# XOR_GATE.net
KiCad netlist of a schematic drawn in Altium Designer
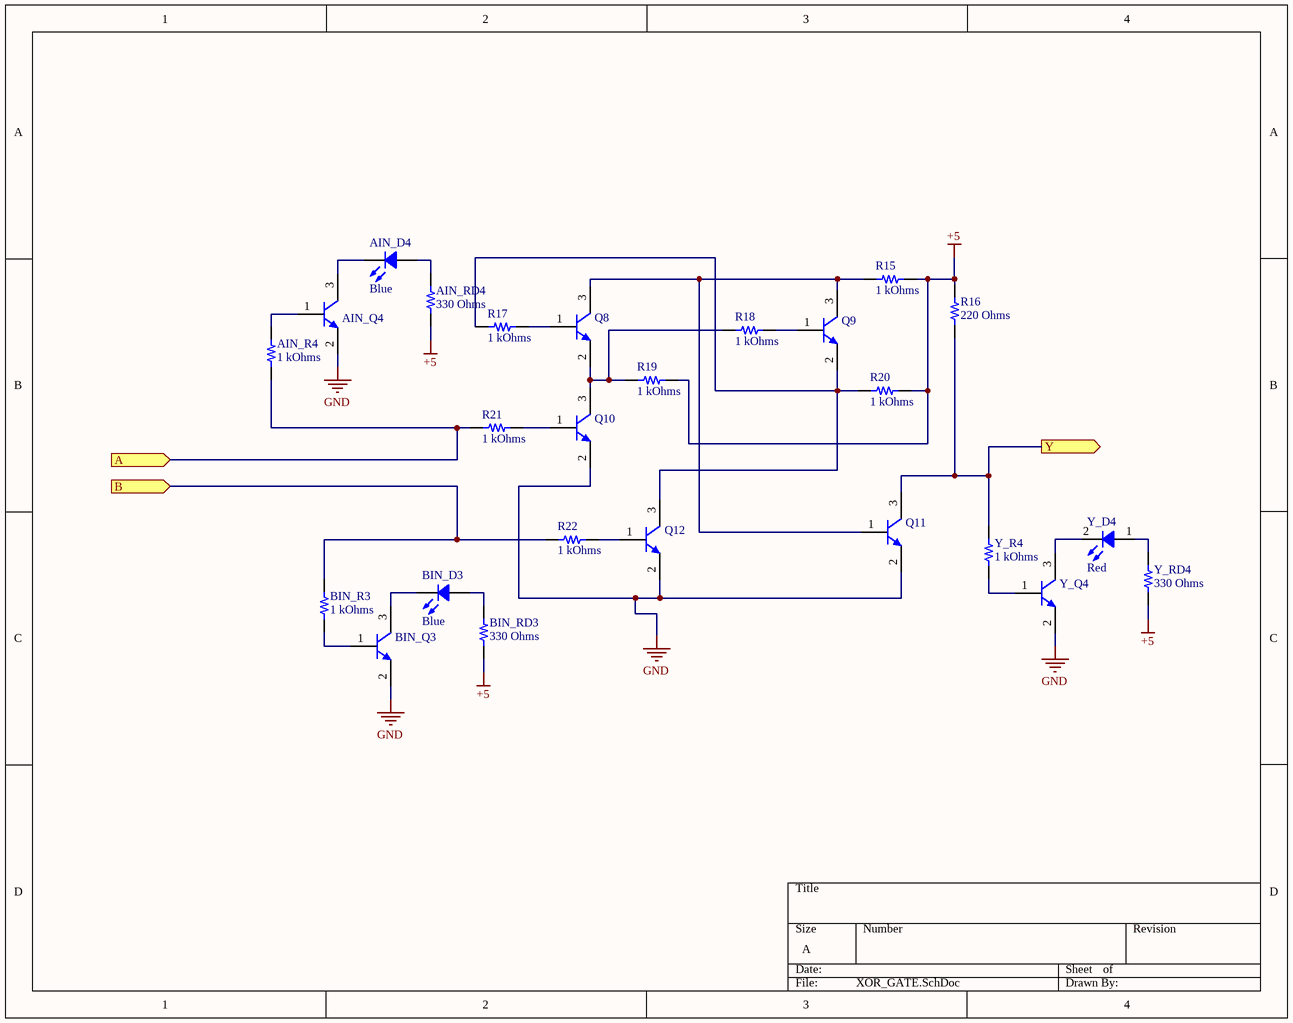
[diagram p0: XOR_GATE.SchDoc]

(export (version "E")
  (design (tool "Eeschema 10.0.6"))
  (components
    (comp (ref "AIN_D4")
      (value "Blue")
      (footprint "LED 0603_1608 BLUE")
      (description "LED BLUE CLEAR 0603 SMD")
      (fields (field (name "PART NUMBER") "IN-S63AT5B") (field (name "MANUFACTURER") "Inolux"))
      (libsource (lib "") (part "LED_1"))
    )
    (comp (ref "AIN_Q4")
      (value "MMSS8050-L-TP")
      (footprint "MCCSEMI SOT-23-3")
      (description "TRANS NPN 25V 1.5A SOT23")
      (fields (field (name "MANUFACTURER") "Micro Commercial Co"))
      (libsource (lib "Celestial Altium Library - altium_library") (part "MCCSEMI NPN SOT-23-3"))
    )
    (comp (ref "AIN_R4")
      (value "1 kOhms")
      (footprint "RES 0603_1608")
      (description "RES SMD 1K OHM 0.1% 1/16W 0603")
      (fields
        (field (name "PART NUMBER") "CPF0603B1K0E")
        (field (name "MANUFACTURER") "TE Connectivity Passive Product")
      )
      (libsource (lib "Celestial Altium Library - altium_library") (part "Resistor"))
    )
    (comp (ref "AIN_RD4")
      (value "330 Ohms")
      (footprint "RES 0603_1608")
      (description "RES 330 OHM 5% 1/10W 0603")
      (fields
        (field (name "PART NUMBER") "RMCF0603JT330R")
        (field (name "MANUFACTURER") "Stackpole Electronics Inc")
      )
      (libsource (lib "Celestial Altium Library - altium_library") (part "Resistor"))
    )
    (comp (ref "BIN_D3")
      (value "Blue")
      (footprint "LED 0603_1608 BLUE")
      (description "LED BLUE CLEAR 0603 SMD")
      (fields (field (name "PART NUMBER") "IN-S63AT5B") (field (name "MANUFACTURER") "Inolux"))
      (libsource (lib "") (part "LED_1"))
    )
    (comp (ref "BIN_Q3")
      (value "MMSS8050-L-TP")
      (footprint "MCCSEMI SOT-23-3")
      (description "TRANS NPN 25V 1.5A SOT23")
      (fields (field (name "MANUFACTURER") "Micro Commercial Co"))
      (libsource (lib "Celestial Altium Library - altium_library") (part "MCCSEMI NPN SOT-23-3"))
    )
    (comp (ref "BIN_R3")
      (value "1 kOhms")
      (footprint "RES 0603_1608")
      (description "RES SMD 1K OHM 0.1% 1/16W 0603")
      (fields
        (field (name "PART NUMBER") "CPF0603B1K0E")
        (field (name "MANUFACTURER") "TE Connectivity Passive Product")
      )
      (libsource (lib "Celestial Altium Library - altium_library") (part "Resistor"))
    )
    (comp (ref "BIN_RD3")
      (value "330 Ohms")
      (footprint "RES 0603_1608")
      (description "RES 330 OHM 5% 1/10W 0603")
      (fields
        (field (name "PART NUMBER") "RMCF0603JT330R")
        (field (name "MANUFACTURER") "Stackpole Electronics Inc")
      )
      (libsource (lib "Celestial Altium Library - altium_library") (part "Resistor"))
    )
    (comp (ref "Q8")
      (value "MMSS8050-L-TP")
      (footprint "MCCSEMI SOT-23-3")
      (description "TRANS NPN 25V 1.5A SOT23")
      (fields (field (name "MANUFACTURER") "Micro Commercial Co"))
      (libsource (lib "Celestial Altium Library - altium_library") (part "MCCSEMI NPN SOT-23-3"))
    )
    (comp (ref "Q9")
      (value "MMSS8050-L-TP")
      (footprint "MCCSEMI SOT-23-3")
      (description "TRANS NPN 25V 1.5A SOT23")
      (fields (field (name "MANUFACTURER") "Micro Commercial Co"))
      (libsource (lib "Celestial Altium Library - altium_library") (part "MCCSEMI NPN SOT-23-3"))
    )
    (comp (ref "Q10")
      (value "MMSS8050-L-TP")
      (footprint "MCCSEMI SOT-23-3")
      (description "TRANS NPN 25V 1.5A SOT23")
      (fields (field (name "MANUFACTURER") "Micro Commercial Co"))
      (libsource (lib "Celestial Altium Library - altium_library") (part "MCCSEMI NPN SOT-23-3"))
    )
    (comp (ref "Q11")
      (value "MMSS8050-L-TP")
      (footprint "MCCSEMI SOT-23-3")
      (description "TRANS NPN 25V 1.5A SOT23")
      (fields (field (name "MANUFACTURER") "Micro Commercial Co"))
      (libsource (lib "Celestial Altium Library - altium_library") (part "MCCSEMI NPN SOT-23-3"))
    )
    (comp (ref "Q12")
      (value "MMSS8050-L-TP")
      (footprint "MCCSEMI SOT-23-3")
      (description "TRANS NPN 25V 1.5A SOT23")
      (fields (field (name "MANUFACTURER") "Micro Commercial Co"))
      (libsource (lib "Celestial Altium Library - altium_library") (part "MCCSEMI NPN SOT-23-3"))
    )
    (comp (ref "R15")
      (value "1 kOhms")
      (footprint "RES 0603_1608")
      (description "RES SMD 1K OHM 0.1% 1/16W 0603")
      (fields
        (field (name "PART NUMBER") "CPF0603B1K0E")
        (field (name "MANUFACTURER") "TE Connectivity Passive Product")
      )
      (libsource (lib "Celestial Altium Library - altium_library") (part "Resistor"))
    )
    (comp (ref "R16")
      (value "220 Ohms")
      (footprint "RES 0603_1608")
      (description "RES SMD 220 OHM 0.5% 1/10W 0603")
      (fields
        (field (name "PART NUMBER") "ERA-3AED221V")
        (field (name "MANUFACTURER") "Panasonic Electronic Components")
      )
      (libsource (lib "Celestial Altium Library - altium_library") (part "Resistor"))
    )
    (comp (ref "R17")
      (value "1 kOhms")
      (footprint "RES 0603_1608")
      (description "RES SMD 1K OHM 0.1% 1/16W 0603")
      (fields
        (field (name "PART NUMBER") "CPF0603B1K0E")
        (field (name "MANUFACTURER") "TE Connectivity Passive Product")
      )
      (libsource (lib "Celestial Altium Library - altium_library") (part "Resistor"))
    )
    (comp (ref "R18")
      (value "1 kOhms")
      (footprint "RES 0603_1608")
      (description "RES SMD 1K OHM 0.1% 1/16W 0603")
      (fields
        (field (name "PART NUMBER") "CPF0603B1K0E")
        (field (name "MANUFACTURER") "TE Connectivity Passive Product")
      )
      (libsource (lib "Celestial Altium Library - altium_library") (part "Resistor"))
    )
    (comp (ref "R19")
      (value "1 kOhms")
      (footprint "RES 0603_1608")
      (description "RES SMD 1K OHM 0.1% 1/16W 0603")
      (fields
        (field (name "PART NUMBER") "CPF0603B1K0E")
        (field (name "MANUFACTURER") "TE Connectivity Passive Product")
      )
      (libsource (lib "Celestial Altium Library - altium_library") (part "Resistor"))
    )
    (comp (ref "R20")
      (value "1 kOhms")
      (footprint "RES 0603_1608")
      (description "RES SMD 1K OHM 0.1% 1/16W 0603")
      (fields
        (field (name "PART NUMBER") "CPF0603B1K0E")
        (field (name "MANUFACTURER") "TE Connectivity Passive Product")
      )
      (libsource (lib "Celestial Altium Library - altium_library") (part "Resistor"))
    )
    (comp (ref "R21")
      (value "1 kOhms")
      (footprint "RES 0603_1608")
      (description "RES SMD 1K OHM 0.1% 1/16W 0603")
      (fields
        (field (name "PART NUMBER") "CPF0603B1K0E")
        (field (name "MANUFACTURER") "TE Connectivity Passive Product")
      )
      (libsource (lib "Celestial Altium Library - altium_library") (part "Resistor"))
    )
    (comp (ref "R22")
      (value "1 kOhms")
      (footprint "RES 0603_1608")
      (description "RES SMD 1K OHM 0.1% 1/16W 0603")
      (fields
        (field (name "PART NUMBER") "CPF0603B1K0E")
        (field (name "MANUFACTURER") "TE Connectivity Passive Product")
      )
      (libsource (lib "Celestial Altium Library - altium_library") (part "Resistor"))
    )
    (comp (ref "Y_D4")
      (value "Red")
      (footprint "LED 0603_1608 RED")
      (description "LED RED CLEAR CHIP SMD")
      (fields (field (name "PART NUMBER") "XZMDK53W-8") (field (name "MANUFACTURER") "SunLED"))
      (libsource (lib "Celestial Altium Library - altium_library") (part "LED"))
    )
    (comp (ref "Y_Q4")
      (value "MMSS8050-L-TP")
      (footprint "MCCSEMI SOT-23-3")
      (description "TRANS NPN 25V 1.5A SOT23")
      (fields (field (name "MANUFACTURER") "Micro Commercial Co"))
      (libsource (lib "Celestial Altium Library - altium_library") (part "MCCSEMI NPN SOT-23-3"))
    )
    (comp (ref "Y_R4")
      (value "1 kOhms")
      (footprint "RES 0603_1608")
      (description "RES SMD 1K OHM 0.1% 1/16W 0603")
      (fields
        (field (name "PART NUMBER") "CPF0603B1K0E")
        (field (name "MANUFACTURER") "TE Connectivity Passive Product")
      )
      (libsource (lib "Celestial Altium Library - altium_library") (part "Resistor"))
    )
    (comp (ref "Y_RD4")
      (value "330 Ohms")
      (footprint "RES 0603_1608")
      (description "RES 330 OHM 5% 1/10W 0603")
      (fields
        (field (name "PART NUMBER") "RMCF0603JT330R")
        (field (name "MANUFACTURER") "Stackpole Electronics Inc")
      )
      (libsource (lib "Celestial Altium Library - altium_library") (part "Resistor"))
    )
  )
  (nets
    (net (code "1") (name "+5") (class "Default")
      (node (ref "AIN_RD4") (pin "1") (pinfunction "1_1") (pintype "passive"))
      (node (ref "BIN_RD3") (pin "1") (pinfunction "1_1") (pintype "passive"))
      (node (ref "R15") (pin "2") (pinfunction "2_2") (pintype "passive"))
      (node (ref "R16") (pin "2") (pinfunction "2_2") (pintype "passive"))
      (node (ref "R19") (pin "2") (pinfunction "2_2") (pintype "passive"))
      (node (ref "R20") (pin "2") (pinfunction "2_2") (pintype "passive"))
      (node (ref "Y_RD4") (pin "1") (pinfunction "1_1") (pintype "passive"))
    )
    (net (code "2") (name "/A") (class "Default")
      (node (ref "AIN_R4") (pin "2") (pinfunction "2_2") (pintype "passive"))
      (node (ref "R21") (pin "1") (pinfunction "1_1") (pintype "passive"))
    )
    (net (code "3") (name "/B") (class "Default")
      (node (ref "BIN_R3") (pin "2") (pinfunction "2_2") (pintype "passive"))
      (node (ref "R22") (pin "1") (pinfunction "1_1") (pintype "passive"))
    )
    (net (code "4") (name "/Y") (class "Default")
      (node (ref "Q11") (pin "3") (pinfunction "C_3") (pintype "passive"))
      (node (ref "R16") (pin "1") (pinfunction "1_1") (pintype "passive"))
      (node (ref "Y_R4") (pin "2") (pinfunction "2_2") (pintype "passive"))
    )
    (net (code "5") (name "GND") (class "Default")
      (node (ref "AIN_Q4") (pin "2") (pinfunction "E_2") (pintype "passive"))
      (node (ref "BIN_Q3") (pin "2") (pinfunction "E_2") (pintype "passive"))
      (node (ref "Q10") (pin "2") (pinfunction "E_2") (pintype "passive"))
      (node (ref "Q11") (pin "2") (pinfunction "E_2") (pintype "passive"))
      (node (ref "Q12") (pin "2") (pinfunction "E_2") (pintype "passive"))
      (node (ref "Y_Q4") (pin "2") (pinfunction "E_2") (pintype "passive"))
    )
    (net (code "6") (name "Net-(AIN_D4-Pad1)") (class "Default")
      (node (ref "AIN_D4") (pin "1") (pinfunction "1_1") (pintype "passive"))
      (node (ref "AIN_RD4") (pin "2") (pinfunction "2_2") (pintype "passive"))
    )
    (net (code "7") (name "Net-(AIN_Q4-B)") (class "Default")
      (node (ref "AIN_Q4") (pin "1") (pinfunction "B_1") (pintype "passive"))
      (node (ref "AIN_R4") (pin "1") (pinfunction "1_1") (pintype "passive"))
    )
    (net (code "8") (name "Net-(AIN_Q4-C)") (class "Default")
      (node (ref "AIN_D4") (pin "2") (pinfunction "2_2") (pintype "passive"))
      (node (ref "AIN_Q4") (pin "3") (pinfunction "C_3") (pintype "passive"))
    )
    (net (code "9") (name "Net-(BIN_D3-Pad1)") (class "Default")
      (node (ref "BIN_D3") (pin "1") (pinfunction "1_1") (pintype "passive"))
      (node (ref "BIN_RD3") (pin "2") (pinfunction "2_2") (pintype "passive"))
    )
    (net (code "10") (name "Net-(BIN_Q3-B)") (class "Default")
      (node (ref "BIN_Q3") (pin "1") (pinfunction "B_1") (pintype "passive"))
      (node (ref "BIN_R3") (pin "1") (pinfunction "1_1") (pintype "passive"))
    )
    (net (code "11") (name "Net-(BIN_Q3-C)") (class "Default")
      (node (ref "BIN_D3") (pin "2") (pinfunction "2_2") (pintype "passive"))
      (node (ref "BIN_Q3") (pin "3") (pinfunction "C_3") (pintype "passive"))
    )
    (net (code "12") (name "Net-(Q8-B)") (class "Default")
      (node (ref "Q8") (pin "1") (pinfunction "B_1") (pintype "passive"))
      (node (ref "R17") (pin "2") (pinfunction "2_2") (pintype "passive"))
    )
    (net (code "13") (name "Net-(Q9-B)") (class "Default")
      (node (ref "Q9") (pin "1") (pinfunction "B_1") (pintype "passive"))
      (node (ref "R18") (pin "2") (pinfunction "2_2") (pintype "passive"))
    )
    (net (code "14") (name "Net-(Q10-B)") (class "Default")
      (node (ref "Q10") (pin "1") (pinfunction "B_1") (pintype "passive"))
      (node (ref "R21") (pin "2") (pinfunction "2_2") (pintype "passive"))
    )
    (net (code "15") (name "Net-(Q10-C)") (class "Default")
      (node (ref "Q10") (pin "3") (pinfunction "C_3") (pintype "passive"))
      (node (ref "Q8") (pin "2") (pinfunction "E_2") (pintype "passive"))
      (node (ref "R18") (pin "1") (pinfunction "1_1") (pintype "passive"))
      (node (ref "R19") (pin "1") (pinfunction "1_1") (pintype "passive"))
    )
    (net (code "16") (name "Net-(Q11-B)") (class "Default")
      (node (ref "Q11") (pin "1") (pinfunction "B_1") (pintype "passive"))
      (node (ref "Q8") (pin "3") (pinfunction "C_3") (pintype "passive"))
      (node (ref "Q9") (pin "3") (pinfunction "C_3") (pintype "passive"))
      (node (ref "R15") (pin "1") (pinfunction "1_1") (pintype "passive"))
    )
    (net (code "17") (name "Net-(Q12-B)") (class "Default")
      (node (ref "Q12") (pin "1") (pinfunction "B_1") (pintype "passive"))
      (node (ref "R22") (pin "2") (pinfunction "2_2") (pintype "passive"))
    )
    (net (code "18") (name "Net-(Q12-C)") (class "Default")
      (node (ref "Q12") (pin "3") (pinfunction "C_3") (pintype "passive"))
      (node (ref "Q9") (pin "2") (pinfunction "E_2") (pintype "passive"))
      (node (ref "R17") (pin "1") (pinfunction "1_1") (pintype "passive"))
      (node (ref "R20") (pin "1") (pinfunction "1_1") (pintype "passive"))
    )
    (net (code "19") (name "Net-(Y_D4-Pad1)") (class "Default")
      (node (ref "Y_D4") (pin "1") (pinfunction "1_1") (pintype "passive"))
      (node (ref "Y_RD4") (pin "2") (pinfunction "2_2") (pintype "passive"))
    )
    (net (code "20") (name "Net-(Y_Q4-B)") (class "Default")
      (node (ref "Y_Q4") (pin "1") (pinfunction "B_1") (pintype "passive"))
      (node (ref "Y_R4") (pin "1") (pinfunction "1_1") (pintype "passive"))
    )
    (net (code "21") (name "Net-(Y_Q4-C)") (class "Default")
      (node (ref "Y_D4") (pin "2") (pinfunction "2_2") (pintype "passive"))
      (node (ref "Y_Q4") (pin "3") (pinfunction "C_3") (pintype "passive"))
    )
  )
)
